# FE_Channel.net
KiCad netlist of a schematic drawn in Altium Designer
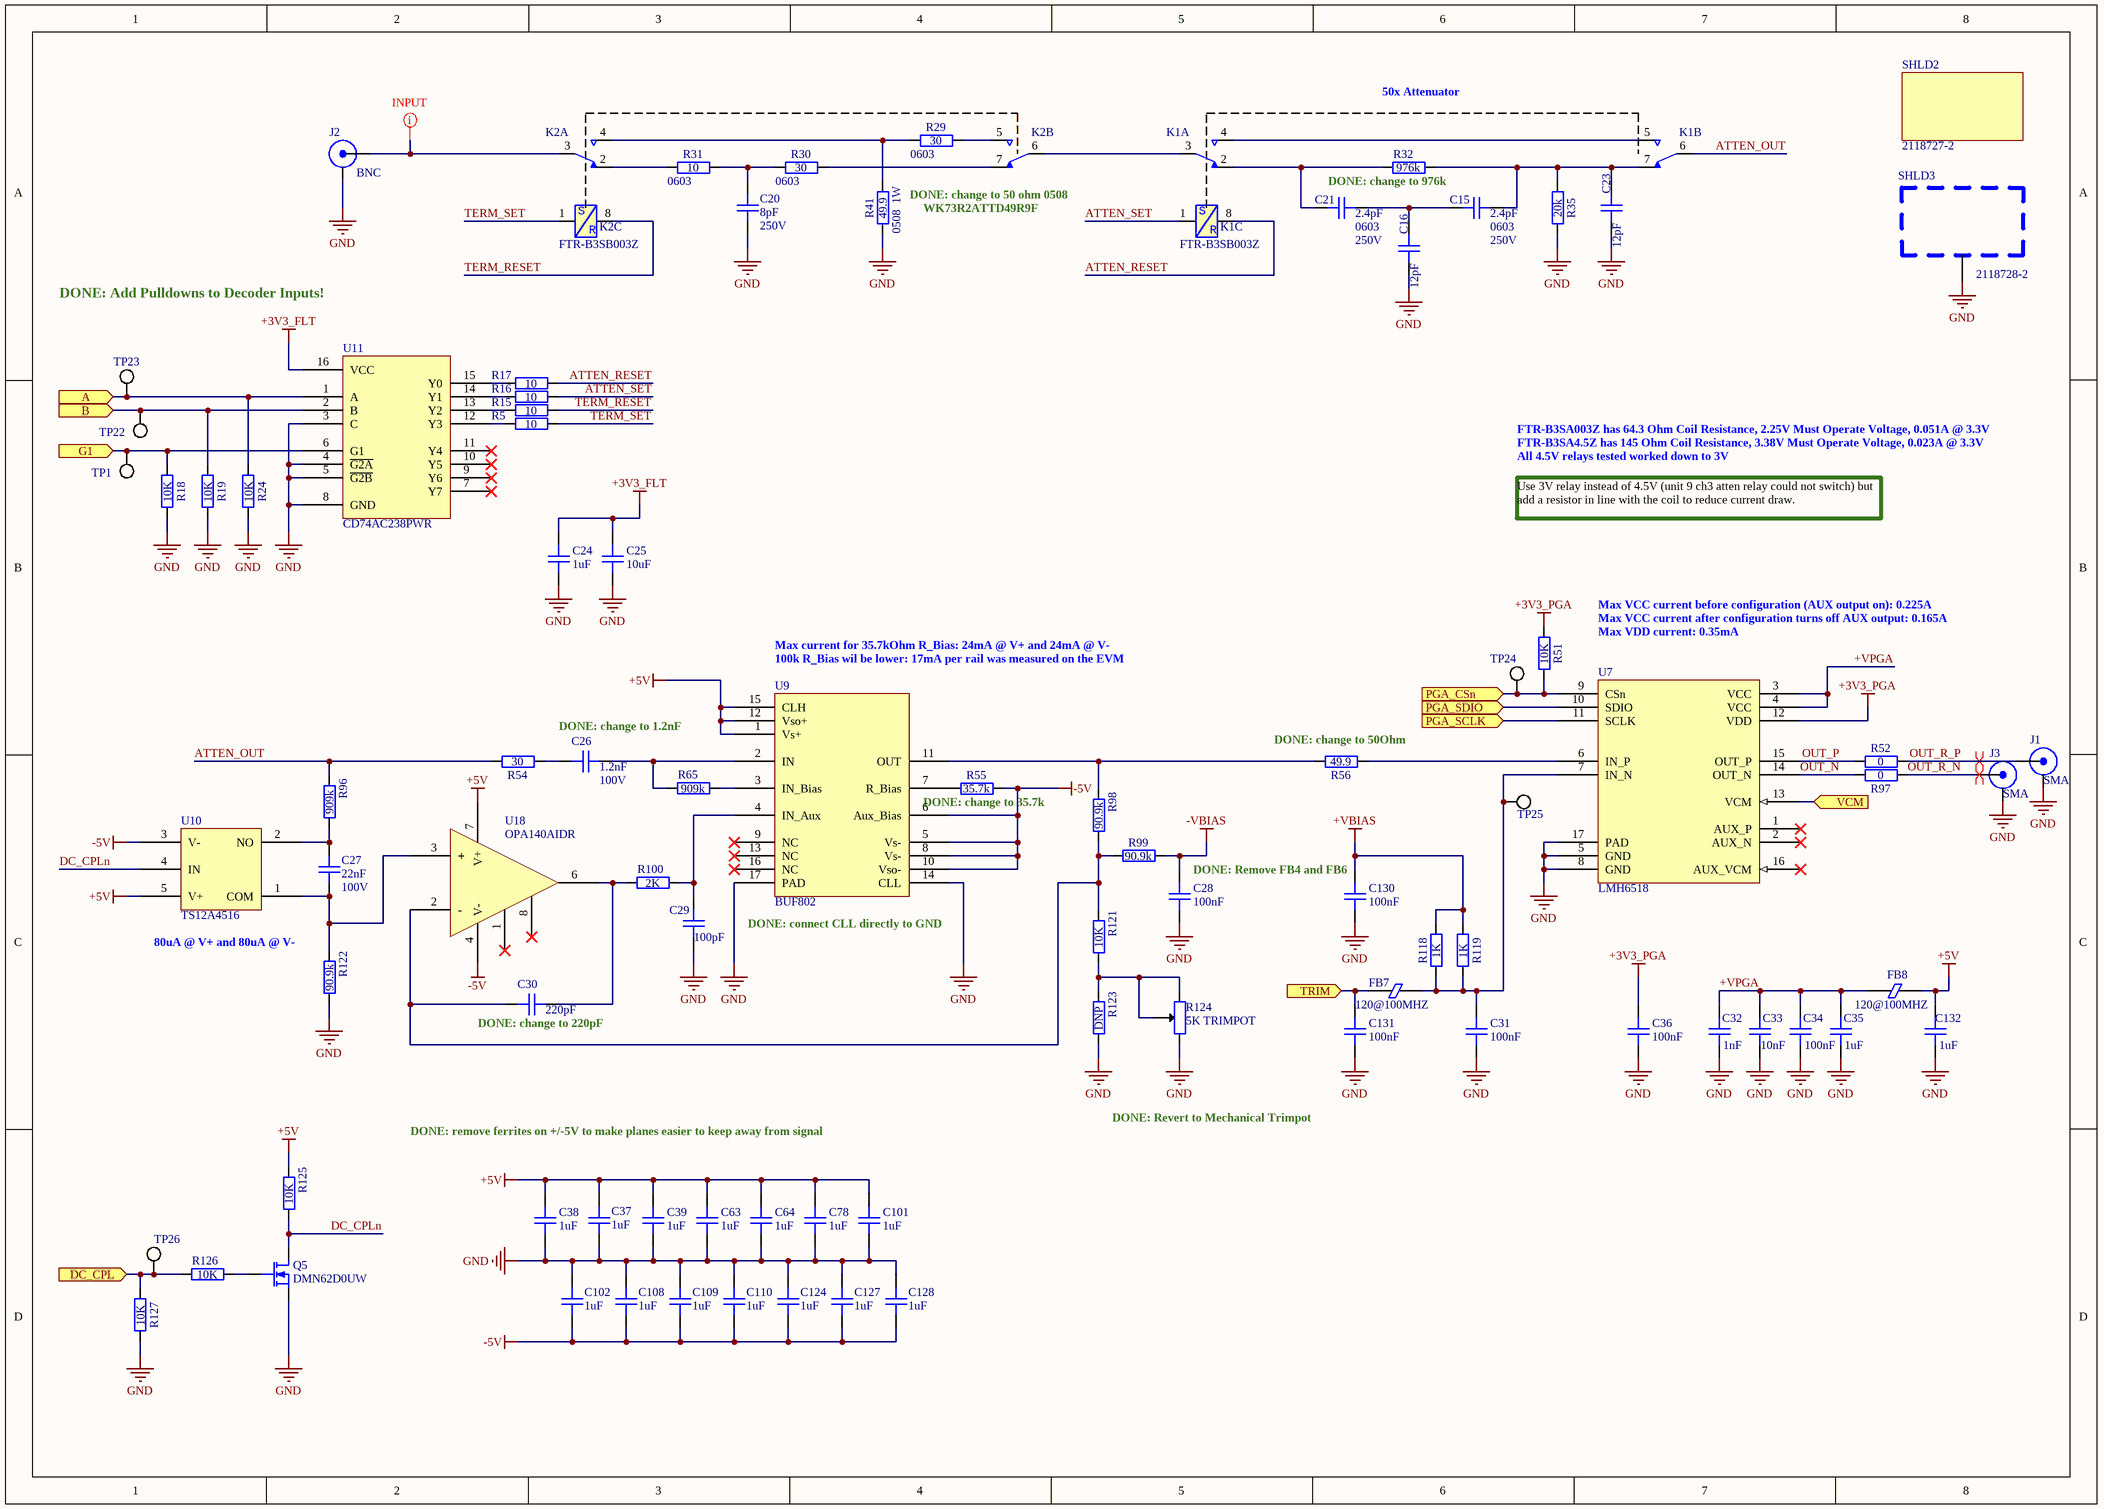
[diagram p0: FE_Channel.SchDoc]

(export (version "E")
  (design (tool "Eeschema 10.0.6"))
  (components
    (comp (ref "C15")
      (value "2.4pF")
      (footprint "GEN_C_0603")
      (fields
        (field (name "PACKAGE") "0603")
        (field (name "VOLTAGE RATING") "250V")
        (field (name "MANUFACTURER") "KEMET")
        (field (name "MANUFACTURER PART NUMBER") "CBR06C249BAGAC")
      )
      (libsource (lib "DSO") (part "CAP 2.4pF 250V C0G 0603"))
    )
    (comp (ref "C16")
      (value "12pF")
      (footprint "GEN_C_0402")
      (fields
        (field (name "MANUFACTURER") "KEMET")
        (field (name "MANUFACTURER PART NUMBER") "CBR04C120F5GAC")
      )
      (libsource (lib "DSO") (part "CAP 12pF 50V C0G 0402"))
    )
    (comp (ref "C20")
      (value "8pF")
      (footprint "GEN_C_0603")
      (fields
        (field (name "MANUFACTURER") "KEMET")
        (field (name "MANUFACTURER PART NUMBER") "CBR06C809BAGAC")
        (field (name "VOLTAGE RATING") "250V")
      )
      (libsource (lib "DSO") (part "CAP 8pF 250V C0G 0603"))
    )
    (comp (ref "C21")
      (value "2.4pF")
      (footprint "GEN_C_0603")
      (fields
        (field (name "PACKAGE") "0603")
        (field (name "VOLTAGE RATING") "250V")
        (field (name "MANUFACTURER") "KEMET")
        (field (name "MANUFACTURER PART NUMBER") "CBR06C249BAGAC")
      )
      (libsource (lib "DSO") (part "CAP 2.4pF 250V C0G 0603"))
    )
    (comp (ref "C23")
      (value "12pF")
      (footprint "GEN_C_0402")
      (fields
        (field (name "MANUFACTURER") "KEMET")
        (field (name "MANUFACTURER PART NUMBER") "CBR04C120F5GAC")
      )
      (libsource (lib "DSO") (part "CAP 12pF 50V C0G 0402"))
    )
    (comp (ref "C24")
      (value "1uF")
      (footprint "GEN_C_0402")
      (fields
        (field (name "MANUFACTURER") "Murata")
        (field (name "MANUFACTURER PART NUMBER") "GRM155R61E105KA12D")
      )
      (libsource (lib "DSO") (part "CAP 1uF 25V X5R 0402"))
    )
    (comp (ref "C25")
      (value "10uF")
      (footprint "GEN_C_0603")
      (fields
        (field (name "HOUSE PART NUMBER") "C-10uF-0603-002")
        (field (name "MANUFACTURER") "Murata")
        (field (name "MANUFACTURER PART NUMBER") "GRM188R61A106ME69D")
      )
      (libsource (lib "DSO") (part "CAP 10uF 10V X5R 0603"))
    )
    (comp (ref "C26")
      (value "1.2nF")
      (footprint "GEN_C_0603")
      (fields
        (field (name "VOLTAGE RATING") "100V")
        (field (name "MANUFACTURER") "Murata")
        (field (name "MANUFACTURER PART NUMBER") "GCM1885C2A122FA16D")
      )
      (libsource (lib "DSO") (part "CAP 1.2nF 100V C0G 0603"))
    )
    (comp (ref "C27")
      (value "22nF")
      (footprint "GEN_C_0603")
      (fields
        (field (name "VOLTAGE RATING") "100V")
        (field (name "MANUFACTURER") "Murata")
        (field (name "MANUFACTURER PART NUMBER") "GCM188R72A223KA37D")
      )
      (libsource (lib "DSO") (part "CAP 22nF 100V X7R 0603"))
    )
    (comp (ref "C28")
      (value "100nF")
      (footprint "GEN_C_0402")
      (fields
        (field (name "HOUSE PART NUMBER") "C-100nF-0402-002")
        (field (name "MANUFACTURER") "Murata")
        (field (name "MANUFACTURER PART NUMBER") "GCM155R71C104KA55D")
      )
      (libsource (lib "DSO") (part "CAP 100nF 16V X7R 0402"))
    )
    (comp (ref "C29")
      (value "100pF")
      (footprint "GEN_C_0402")
      (fields
        (field (name "MANUFACTURER") "Murata")
        (field (name "MANUFACTURER PART NUMBER") "GCM1555C1H101FA16D")
      )
      (libsource (lib "DSO") (part "CAP 100pF 50V C0G 0402"))
    )
    (comp (ref "C30")
      (value "220pF")
      (footprint "GEN_C_0402")
      (fields
        (field (name "MANUFACTURER") "Murata")
        (field (name "MANUFACTURER PART NUMBER") "GCM1555C1H221FA16J")
      )
      (libsource (lib "DSO") (part "CAP 220pF 50V C0G 0402"))
    )
    (comp (ref "C31")
      (value "100nF")
      (footprint "GEN_C_0402")
      (fields
        (field (name "HOUSE PART NUMBER") "C-100nF-0402-002")
        (field (name "MANUFACTURER") "Murata")
        (field (name "MANUFACTURER PART NUMBER") "GCM155R71C104KA55D")
      )
      (libsource (lib "DSO") (part "CAP 100nF 16V X7R 0402"))
    )
    (comp (ref "C32")
      (value "1nF")
      (footprint "GEN_C_0402")
      (fields
        (field (name "MANUFACTURER") "Murata")
        (field (name "MANUFACTURER PART NUMBER") "GRM1555C1H102FA01D")
      )
      (libsource (lib "DSO") (part "CAP 1nF 50V C0G 0402"))
    )
    (comp (ref "C33")
      (value "10nF")
      (footprint "GEN_C_0402")
      (fields
        (field (name "HOUSE PART NUMBER") "C-10nF-0402-002")
        (field (name "MANUFACTURER") "Murata")
        (field (name "MANUFACTURER PART NUMBER") "GRM155R71H103KA88J")
      )
      (libsource (lib "DSO") (part "CAP 10nF 50V X7R 0402"))
    )
    (comp (ref "C34")
      (value "100nF")
      (footprint "GEN_C_0402")
      (fields
        (field (name "HOUSE PART NUMBER") "C-100nF-0402-002")
        (field (name "MANUFACTURER") "Murata")
        (field (name "MANUFACTURER PART NUMBER") "GCM155R71C104KA55D")
      )
      (libsource (lib "DSO") (part "CAP 100nF 16V X7R 0402"))
    )
    (comp (ref "C35")
      (value "1uF")
      (footprint "GEN_C_0402")
      (fields
        (field (name "MANUFACTURER") "Murata")
        (field (name "MANUFACTURER PART NUMBER") "GRM155R61E105KA12D")
      )
      (libsource (lib "DSO") (part "CAP 1uF 25V X5R 0402"))
    )
    (comp (ref "C36")
      (value "100nF")
      (footprint "GEN_C_0402")
      (fields
        (field (name "HOUSE PART NUMBER") "C-100nF-0402-002")
        (field (name "MANUFACTURER") "Murata")
        (field (name "MANUFACTURER PART NUMBER") "GCM155R71C104KA55D")
      )
      (libsource (lib "DSO") (part "CAP 100nF 16V X7R 0402"))
    )
    (comp (ref "C37")
      (value "1uF")
      (footprint "GEN_C_0402")
      (fields
        (field (name "MANUFACTURER") "Murata")
        (field (name "MANUFACTURER PART NUMBER") "GRM155R61E105KA12D")
      )
      (libsource (lib "DSO") (part "CAP 1uF 25V X5R 0402"))
    )
    (comp (ref "C38")
      (value "1uF")
      (footprint "GEN_C_0402")
      (fields
        (field (name "MANUFACTURER") "Murata")
        (field (name "MANUFACTURER PART NUMBER") "GRM155R61E105KA12D")
      )
      (libsource (lib "DSO") (part "CAP 1uF 25V X5R 0402"))
    )
    (comp (ref "C39")
      (value "1uF")
      (footprint "GEN_C_0402")
      (fields
        (field (name "MANUFACTURER") "Murata")
        (field (name "MANUFACTURER PART NUMBER") "GRM155R61E105KA12D")
      )
      (libsource (lib "DSO") (part "CAP 1uF 25V X5R 0402"))
    )
    (comp (ref "C63")
      (value "1uF")
      (footprint "GEN_C_0402")
      (fields
        (field (name "MANUFACTURER") "Murata")
        (field (name "MANUFACTURER PART NUMBER") "GRM155R61E105KA12D")
      )
      (libsource (lib "DSO") (part "CAP 1uF 25V X5R 0402"))
    )
    (comp (ref "C64")
      (value "1uF")
      (footprint "GEN_C_0402")
      (fields
        (field (name "MANUFACTURER") "Murata")
        (field (name "MANUFACTURER PART NUMBER") "GRM155R61E105KA12D")
      )
      (libsource (lib "DSO") (part "CAP 1uF 25V X5R 0402"))
    )
    (comp (ref "C78")
      (value "1uF")
      (footprint "GEN_C_0402")
      (fields
        (field (name "MANUFACTURER") "Murata")
        (field (name "MANUFACTURER PART NUMBER") "GRM155R61E105KA12D")
      )
      (libsource (lib "DSO") (part "CAP 1uF 25V X5R 0402"))
    )
    (comp (ref "C101")
      (value "1uF")
      (footprint "GEN_C_0402")
      (fields
        (field (name "MANUFACTURER") "Murata")
        (field (name "MANUFACTURER PART NUMBER") "GRM155R61E105KA12D")
      )
      (libsource (lib "DSO") (part "CAP 1uF 25V X5R 0402"))
    )
    (comp (ref "C102")
      (value "1uF")
      (footprint "GEN_C_0402")
      (fields
        (field (name "MANUFACTURER") "Murata")
        (field (name "MANUFACTURER PART NUMBER") "GRM155R61E105KA12D")
      )
      (libsource (lib "DSO") (part "CAP 1uF 25V X5R 0402"))
    )
    (comp (ref "C108")
      (value "1uF")
      (footprint "GEN_C_0402")
      (fields
        (field (name "MANUFACTURER") "Murata")
        (field (name "MANUFACTURER PART NUMBER") "GRM155R61E105KA12D")
      )
      (libsource (lib "DSO") (part "CAP 1uF 25V X5R 0402"))
    )
    (comp (ref "C109")
      (value "1uF")
      (footprint "GEN_C_0402")
      (fields
        (field (name "MANUFACTURER") "Murata")
        (field (name "MANUFACTURER PART NUMBER") "GRM155R61E105KA12D")
      )
      (libsource (lib "DSO") (part "CAP 1uF 25V X5R 0402"))
    )
    (comp (ref "C110")
      (value "1uF")
      (footprint "GEN_C_0402")
      (fields
        (field (name "MANUFACTURER") "Murata")
        (field (name "MANUFACTURER PART NUMBER") "GRM155R61E105KA12D")
      )
      (libsource (lib "DSO") (part "CAP 1uF 25V X5R 0402"))
    )
    (comp (ref "C124")
      (value "1uF")
      (footprint "GEN_C_0402")
      (fields
        (field (name "MANUFACTURER") "Murata")
        (field (name "MANUFACTURER PART NUMBER") "GRM155R61E105KA12D")
      )
      (libsource (lib "DSO") (part "CAP 1uF 25V X5R 0402"))
    )
    (comp (ref "C127")
      (value "1uF")
      (footprint "GEN_C_0402")
      (fields
        (field (name "MANUFACTURER") "Murata")
        (field (name "MANUFACTURER PART NUMBER") "GRM155R61E105KA12D")
      )
      (libsource (lib "DSO") (part "CAP 1uF 25V X5R 0402"))
    )
    (comp (ref "C128")
      (value "1uF")
      (footprint "GEN_C_0402")
      (fields
        (field (name "MANUFACTURER") "Murata")
        (field (name "MANUFACTURER PART NUMBER") "GRM155R61E105KA12D")
      )
      (libsource (lib "DSO") (part "CAP 1uF 25V X5R 0402"))
    )
    (comp (ref "C130")
      (value "100nF")
      (footprint "GEN_C_0402")
      (fields
        (field (name "HOUSE PART NUMBER") "C-100nF-0402-002")
        (field (name "MANUFACTURER") "Murata")
        (field (name "MANUFACTURER PART NUMBER") "GCM155R71C104KA55D")
      )
      (libsource (lib "DSO") (part "CAP 100nF 16V X7R 0402"))
    )
    (comp (ref "C131")
      (value "100nF")
      (footprint "GEN_C_0402")
      (fields
        (field (name "HOUSE PART NUMBER") "C-100nF-0402-002")
        (field (name "MANUFACTURER") "Murata")
        (field (name "MANUFACTURER PART NUMBER") "GCM155R71C104KA55D")
      )
      (libsource (lib "DSO") (part "CAP 100nF 16V X7R 0402"))
    )
    (comp (ref "C132")
      (value "1uF")
      (footprint "GEN_C_0402")
      (fields
        (field (name "MANUFACTURER") "Murata")
        (field (name "MANUFACTURER PART NUMBER") "GRM155R61E105KA12D")
      )
      (libsource (lib "DSO") (part "CAP 1uF 25V X5R 0402"))
    )
    (comp (ref "FB7")
      (value "120@100MHZ")
      (footprint "GEN_R_0402")
      (fields (field (name "HOUSE PART NUMBER") "BLM15PX121SN1D") (field (name "MANUFACTURER") "Murata"))
      (libsource (lib "DSO") (part "FERRITE BEAD 120 OHM 0402"))
    )
    (comp (ref "FB8")
      (value "120@100MHZ")
      (footprint "GEN_R_0402")
      (fields (field (name "HOUSE PART NUMBER") "BLM15PX121SN1D") (field (name "MANUFACTURER") "Murata"))
      (libsource (lib "DSO") (part "FERRITE BEAD 120 OHM 0402"))
    )
    (comp (ref "J1")
      (value "SMA")
      (footprint "MOL_0733910083")
      (fields (field (name "MANUFACTURER") "Molex") (field (name "MANUFACTURER PART NUMBER") "73100-0105"))
      (libsource (lib "DSO") (part "SMA JACK R/A"))
    )
    (comp (ref "J2")
      (value "BNC")
      (footprint "MOL_0731000105")
      (fields (field (name "MANUFACTURER") "Molex") (field (name "MANUFACTURER PART NUMBER") "73100-0105"))
      (libsource (lib "DSO") (part "BNC JACK R/A"))
    )
    (comp (ref "J3")
      (value "SMA")
      (footprint "MOL_0733910083")
      (fields (field (name "MANUFACTURER") "Molex") (field (name "MANUFACTURER PART NUMBER") "73100-0105"))
      (libsource (lib "DSO") (part "SMA JACK R/A"))
    )
    (comp (ref "K1")
      (value "FTR-B3SB003Z")
      (footprint "FUJ_FTR-B3SA")
      (fields (field (name "MANUFACTURER") "Fujitsu"))
      (libsource (lib "") (part "RELAY DPDT-NO FTR-B3SB003Z_1"))
    )
    (comp (ref "K2")
      (value "FTR-B3SB003Z")
      (footprint "FUJ_FTR-B3SA")
      (fields (field (name "MANUFACTURER") "Fujitsu"))
      (libsource (lib "") (part "RELAY DPDT-NO FTR-B3SB003Z_1"))
    )
    (comp (ref "Q5")
      (value "DMN62D0UW")
      (footprint "GEN_SOT_323")
      (fields (field (name "HOUSE PART NUMBER") "DMN62D0UW-7") (field (name "MANUFACTURER") "Diodes"))
      (libsource (lib "DSO") (part "NMOS DMN62D0UW"))
    )
    (comp (ref "R5")
      (value "10")
      (footprint "GEN_R_0603")
      (fields
        (field (name "TOLERANCE") "1%")
        (field (name "MANUFACTURER") "KOA Speer")
        (field (name "MANUFACTURER PART NUMBER") "SG73P1JTTD10R0F")
      )
      (libsource (lib "DSO") (part "RES 10 OHM 1% 1/3W 0603"))
    )
    (comp (ref "R15")
      (value "10")
      (footprint "GEN_R_0603")
      (fields
        (field (name "TOLERANCE") "1%")
        (field (name "MANUFACTURER") "KOA Speer")
        (field (name "MANUFACTURER PART NUMBER") "SG73P1JTTD10R0F")
      )
      (libsource (lib "DSO") (part "RES 10 OHM 1% 1/3W 0603"))
    )
    (comp (ref "R16")
      (value "10")
      (footprint "GEN_R_0603")
      (fields
        (field (name "TOLERANCE") "1%")
        (field (name "MANUFACTURER") "KOA Speer")
        (field (name "MANUFACTURER PART NUMBER") "SG73P1JTTD10R0F")
      )
      (libsource (lib "DSO") (part "RES 10 OHM 1% 1/3W 0603"))
    )
    (comp (ref "R17")
      (value "10")
      (footprint "GEN_R_0603")
      (fields
        (field (name "TOLERANCE") "1%")
        (field (name "MANUFACTURER") "KOA Speer")
        (field (name "MANUFACTURER PART NUMBER") "SG73P1JTTD10R0F")
      )
      (libsource (lib "DSO") (part "RES 10 OHM 1% 1/3W 0603"))
    )
    (comp (ref "R18")
      (value "10K")
      (footprint "GEN_R_0402")
      (fields
        (field (name "TOLERANCE") "1%")
        (field (name "MANUFACTURER") "Panasonic")
        (field (name "MANUFACTURER PART NUMBER") "ERJ-2RKF1002X")
      )
      (libsource (lib "") (part "RES 10K OHM 1% 1/10W 0402_1"))
    )
    (comp (ref "R19")
      (value "10K")
      (footprint "GEN_R_0402")
      (fields
        (field (name "TOLERANCE") "1%")
        (field (name "MANUFACTURER") "Panasonic")
        (field (name "MANUFACTURER PART NUMBER") "ERJ-2RKF1002X")
      )
      (libsource (lib "") (part "RES 10K OHM 1% 1/10W 0402_1"))
    )
    (comp (ref "R24")
      (value "10K")
      (footprint "GEN_R_0402")
      (fields
        (field (name "TOLERANCE") "1%")
        (field (name "MANUFACTURER") "Panasonic")
        (field (name "MANUFACTURER PART NUMBER") "ERJ-2RKF1002X")
      )
      (libsource (lib "") (part "RES 10K OHM 1% 1/10W 0402_1"))
    )
    (comp (ref "R29")
      (value "30")
      (footprint "GEN_R_0603")
      (fields
        (field (name "TOLERANCE") "1%")
        (field (name "PACKAGE") "0603")
        (field (name "MANUFACTURER") "KOA Speer")
        (field (name "MANUFACTURER PART NUMBER") "SG73P1JTTD30R0F")
      )
      (libsource (lib "DSO") (part "RES 30 OHM 1% 1/3W 0603"))
    )
    (comp (ref "R30")
      (value "30")
      (footprint "GEN_R_0603")
      (fields
        (field (name "TOLERANCE") "1%")
        (field (name "PACKAGE") "0603")
        (field (name "MANUFACTURER") "KOA Speer")
        (field (name "MANUFACTURER PART NUMBER") "SG73P1JTTD30R0F")
      )
      (libsource (lib "DSO") (part "RES 30 OHM 1% 1/3W 0603"))
    )
    (comp (ref "R31")
      (value "10")
      (footprint "GEN_R_0603")
      (fields
        (field (name "TOLERANCE") "1%")
        (field (name "PACKAGE") "0603")
        (field (name "MANUFACTURER") "KOA Speer")
        (field (name "MANUFACTURER PART NUMBER") "SG73P1JTTD10R0F")
      )
      (libsource (lib "") (part "RES 10 OHM 1% 1/3W 0603_1"))
    )
    (comp (ref "R32")
      (value "976k")
      (footprint "GEN_R_0603")
      (fields
        (field (name "MANUFACTURER") "KOA Speer")
        (field (name "MANUFACTURER PART NUMBER") "RK73H1JTTD9763F")
        (field (name "TOLERANCE") "1%")
      )
      (libsource (lib "DSO") (part "RES 976k OHM 1% 1/10W 0603"))
    )
    (comp (ref "R35")
      (value "20k")
      (footprint "GEN_R_0402")
      (fields
        (field (name "TOLERANCE") "1%")
        (field (name "MANUFACTURER") "Yageo")
        (field (name "MANUFACTURER PART NUMBER") "RC0402FR-0720KL")
      )
      (libsource (lib "DSO") (part "RES 20K OHM 1% 1/16W 0402"))
    )
    (comp (ref "R41")
      (value "49.9")
      (footprint "GEN_R_0508")
      (fields
        (field (name "TOLERANCE") "1%")
        (field (name "PACKAGE") "0508")
        (field (name "MANUFACTURER") "KOA Speer")
        (field (name "MANUFACTURER PART NUMBER") "WK73R2ATTD49R9F")
        (field (name "POWER RATING") "1W")
      )
      (libsource (lib "DSO") (part "RES 49.9 OHM 1% 1W 0508"))
    )
    (comp (ref "R51")
      (value "10K")
      (footprint "GEN_R_0402")
      (fields
        (field (name "TOLERANCE") "1%")
        (field (name "MANUFACTURER") "Panasonic")
        (field (name "MANUFACTURER PART NUMBER") "ERJ-2RKF1002X")
      )
      (libsource (lib "DSO") (part "RES 10K OHM 1% 1/10W 0402"))
    )
    (comp (ref "R52")
      (value "0")
      (footprint "GEN_R_0402")
      (fields
        (field (name "MANUFACTURER") "Yageo")
        (field (name "MANUFACTURER PART NUMBER") "RC0402JR-070RL")
      )
      (libsource (lib "DSO") (part "RES 0 OHM 1/16W 0402"))
    )
    (comp (ref "R54")
      (value "30")
      (footprint "GEN_R_0603")
      (fields
        (field (name "TOLERANCE") "1%")
        (field (name "MANUFACTURER") "KOA Speer")
        (field (name "MANUFACTURER PART NUMBER") "SG73P1JTTD30R0F")
      )
      (libsource (lib "DSO") (part "RES 30 OHM 1% 1/3W 0603"))
    )
    (comp (ref "R55")
      (value "35.7k")
      (footprint "GEN_R_0402")
      (fields
        (field (name "TOLERANCE") "1%")
        (field (name "MANUFACTURER") "Yageo")
        (field (name "MANUFACTURER PART NUMBER") "RC0402FR-0735K7L")
      )
      (libsource (lib "DSO") (part "RES 35.7K OHM 1% 1/16W 0402"))
    )
    (comp (ref "R56")
      (value "49.9")
      (footprint "GEN_R_0402")
      (fields
        (field (name "MANUFACTURER") "Yageo")
        (field (name "MANUFACTURER PART NUMBER") "RC0402FR-0749R9L")
        (field (name "TOLERANCE") "1%")
      )
      (libsource (lib "DSO") (part "RES 49.9 OHM 1% 1/10W 0402"))
    )
    (comp (ref "R65")
      (value "909k")
      (footprint "GEN_R_0402")
      (fields
        (field (name "TOLERANCE") "1%")
        (field (name "MANUFACTURER") "Yageo")
        (field (name "MANUFACTURER PART NUMBER") "RC0402FR-07909KL")
      )
      (libsource (lib "") (part "RES 909K OHM 1% 1/16W 0402_1"))
    )
    (comp (ref "R96")
      (value "909k")
      (footprint "GEN_R_0402")
      (fields
        (field (name "TOLERANCE") "1%")
        (field (name "MANUFACTURER") "Yageo")
        (field (name "MANUFACTURER PART NUMBER") "RC0402FR-07909KL")
      )
      (libsource (lib "DSO") (part "RES 909K OHM 1% 1/16W 0402"))
    )
    (comp (ref "R97")
      (value "0")
      (footprint "GEN_R_0402")
      (fields
        (field (name "MANUFACTURER") "Yageo")
        (field (name "MANUFACTURER PART NUMBER") "RC0402JR-070RL")
      )
      (libsource (lib "DSO") (part "RES 0 OHM 1/16W 0402"))
    )
    (comp (ref "R98")
      (value "90.9k")
      (footprint "GEN_R_0402")
      (fields
        (field (name "TOLERANCE") "1%")
        (field (name "MANUFACTURER") "Yageo")
        (field (name "MANUFACTURER PART NUMBER") "RC0402FR-0790K9L")
      )
      (libsource (lib "DSO") (part "RES 90.9K OHM 1% 1/16W 0402"))
    )
    (comp (ref "R99")
      (value "90.9k")
      (footprint "GEN_R_0402")
      (fields
        (field (name "TOLERANCE") "1%")
        (field (name "MANUFACTURER") "Yageo")
        (field (name "MANUFACTURER PART NUMBER") "RC0402FR-0790K9L")
      )
      (libsource (lib "") (part "RES 90.9K OHM 1% 1/16W 0402_1"))
    )
    (comp (ref "R100")
      (value "2K")
      (footprint "GEN_R_0402")
      (fields
        (field (name "TOLERANCE") "1%")
        (field (name "MANUFACTURER") "Yageo")
        (field (name "MANUFACTURER PART NUMBER") "RC0402FR-072KL")
      )
      (libsource (lib "DSO") (part "RES 2K OHM 1% 1/16W 0402"))
    )
    (comp (ref "R118")
      (value "1K")
      (footprint "GEN_R_0402")
      (fields
        (field (name "TOLERANCE") "1%")
        (field (name "HOUSE PART NUMBER") "R-1K-0402-1%-001")
        (field (name "MANUFACTURER") "Yageo")
      )
      (libsource (lib "DSO") (part "RES 1K OHM 1% 1/10W 0402"))
    )
    (comp (ref "R119")
      (value "1K")
      (footprint "GEN_R_0402")
      (fields
        (field (name "TOLERANCE") "1%")
        (field (name "HOUSE PART NUMBER") "R-1K-0402-1%-001")
        (field (name "MANUFACTURER") "Yageo")
      )
      (libsource (lib "") (part "RES 1K OHM 1% 1/10W 0402_1"))
    )
    (comp (ref "R121")
      (value "10K")
      (footprint "GEN_R_0402")
      (fields
        (field (name "TOLERANCE") "1%")
        (field (name "MANUFACTURER") "Panasonic")
        (field (name "MANUFACTURER PART NUMBER") "ERJ-2RKF1002X")
      )
      (libsource (lib "DSO") (part "RES 10K OHM 1% 1/10W 0402"))
    )
    (comp (ref "R122")
      (value "90.9k")
      (footprint "GEN_R_0402")
      (fields
        (field (name "TOLERANCE") "1%")
        (field (name "MANUFACTURER") "Yageo")
        (field (name "MANUFACTURER PART NUMBER") "RC0402FR-0790K9L")
      )
      (libsource (lib "DSO") (part "RES 90.9K OHM 1% 1/16W 0402"))
    )
    (comp (ref "R123")
      (value "DNP")
      (footprint "GEN_R_0402")
      (fields (field (name "TOLERANCE") "1%"))
      (libsource (lib "DSO") (part "RES DNP 0402"))
    )
    (comp (ref "R124")
      (value "5K TRIMPOT")
      (footprint "BOU_3mm_POT")
      (fields
        (field (name "TOLERANCE") "1%")
        (field (name "MANUFACTURER") "Bourns")
        (field (name "MANUFACTURER PART NUMBER") "TC33X-2-502E")
      )
      (libsource (lib "DSO") (part "TRIMMER 5K OHM 0.1W J LEAD TOP"))
    )
    (comp (ref "R125")
      (value "10K")
      (footprint "GEN_R_0402")
      (fields
        (field (name "TOLERANCE") "1%")
        (field (name "MANUFACTURER") "Panasonic")
        (field (name "MANUFACTURER PART NUMBER") "ERJ-2RKF1002X")
      )
      (libsource (lib "DSO") (part "RES 10K OHM 1% 1/10W 0402"))
    )
    (comp (ref "R126")
      (value "10K")
      (footprint "GEN_R_0402")
      (fields
        (field (name "TOLERANCE") "1%")
        (field (name "MANUFACTURER") "Panasonic")
        (field (name "MANUFACTURER PART NUMBER") "ERJ-2RKF1002X")
      )
      (libsource (lib "") (part "RES 10K OHM 1% 1/10W 0402_2"))
    )
    (comp (ref "R127")
      (value "10K")
      (footprint "GEN_R_0402")
      (fields
        (field (name "TOLERANCE") "1%")
        (field (name "MANUFACTURER") "Panasonic")
        (field (name "MANUFACTURER PART NUMBER") "ERJ-2RKF1002X")
      )
      (libsource (lib "") (part "RES 10K OHM 1% 1/10W 0402_1"))
    )
    (comp (ref "SHLD2")
      (value "2118727-2")
      (fields (field (name "MANUFACTURER") "TE Connectivity AMP"))
      (libsource (lib "DSO") (part "SHIELD 2118727-2"))
    )
    (comp (ref "SHLD3")
      (value "2118728-2")
      (footprint "TE_2118728-2")
      (fields (field (name "MANUFACTURER") "TE Connectivity"))
      (libsource (lib "DSO") (part "SHIELD 2118728-2"))
    )
    (comp (ref "TP1") (value "PCB") (footprint "GEN_TP_PCB") (libsource (lib "DSO") (part "TP PCB 1mm")))
    (comp (ref "TP22") (value "PCB") (footprint "GEN_TP_PCB") (libsource (lib "DSO") (part "TP PCB 1mm")))
    (comp (ref "TP23") (value "PCB") (footprint "GEN_TP_PCB") (libsource (lib "DSO") (part "TP PCB 1mm")))
    (comp (ref "TP24") (value "PCB") (footprint "GEN_TP_PCB") (libsource (lib "DSO") (part "TP PCB 1mm")))
    (comp (ref "TP25") (value "PCB") (footprint "GEN_TP_PCB") (libsource (lib "DSO") (part "TP PCB 1mm")))
    (comp (ref "TP26") (value "PCB") (footprint "GEN_TP_PCB") (libsource (lib "DSO") (part "TP PCB 1mm")))
    (comp (ref "U7")
      (value "LMH6518")
      (footprint "TI_WQFN_RGH0016A")
      (fields
        (field (name "MANUFACTURER") "Texas Instruments")
        (field (name "MANUFACTURER PART NUMBER") "LMH6518SQE/NOPB")
      )
      (libsource (lib "DSO") (part "IC PGA LMH6518"))
    )
    (comp (ref "U9")
      (value "BUF802")
      (footprint "TI_VQFN_RGT0016C")
      (fields
        (field (name "MANUFACTURER") "Texas Instruments")
        (field (name "MANUFACTURER PART NUMBER") "BUF802IRGTR")
      )
      (libsource (lib "DSO") (part "IC BUFFER AMP BUF802"))
    )
    (comp (ref "U10")
      (value "TS12A4516")
      (footprint "GEN_SOT23_5_950_2900X1600X1450")
      (fields
        (field (name "MANUFACTURER") "Texas Instruments")
        (field (name "MANUFACTURER PART NUMBER") "TS12A4516DBVR")
      )
      (libsource (lib "DSO") (part "IC SWITCH SPST TS12A4516DBVR"))
    )
    (comp (ref "U11")
      (value "CD74AC238PWR")
      (footprint "TI_TSSOP16_PW0016A")
      (fields (field (name "MANUFACTURER") "Texas Instruments"))
      (libsource (lib "DSO") (part "IC Decoder CD74AC238"))
    )
    (comp (ref "U18")
      (value "OPA140AIDR")
      (footprint "TI_SOIC8_D0008A")
      (fields (field (name "MANUFACTURER") "Texas Instruments"))
      (libsource (lib "DSO") (part "IC OPAMP OPA140"))
    )
  )
  (nets
    (net (code "1") (name "+3V3_FLT") (class "Default")
      (node (ref "C24") (pin "2") (pinfunction "2_2") (pintype "passive"))
      (node (ref "C25") (pin "2") (pinfunction "2_2") (pintype "passive"))
      (node (ref "U11") (pin "16") (pinfunction "VCC_16") (pintype "passive"))
    )
    (net (code "2") (name "+3V3_PGA") (class "Default")
      (node (ref "C36") (pin "2") (pinfunction "2_2") (pintype "passive"))
      (node (ref "R51") (pin "2") (pinfunction "2_2") (pintype "passive"))
      (node (ref "U7") (pin "12") (pinfunction "VDD_12") (pintype "power_in"))
    )
    (net (code "3") (name "+5V") (class "Default")
      (node (ref "C101") (pin "2") (pinfunction "2_2") (pintype "passive"))
      (node (ref "C132") (pin "2") (pinfunction "2_2") (pintype "passive"))
      (node (ref "C37") (pin "2") (pinfunction "2_2") (pintype "passive"))
      (node (ref "C38") (pin "1") (pinfunction "1_1") (pintype "passive"))
      (node (ref "C39") (pin "1") (pinfunction "1_1") (pintype "passive"))
      (node (ref "C63") (pin "1") (pinfunction "1_1") (pintype "passive"))
      (node (ref "C64") (pin "2") (pinfunction "2_2") (pintype "passive"))
      (node (ref "C78") (pin "2") (pinfunction "2_2") (pintype "passive"))
      (node (ref "FB8") (pin "2") (pinfunction "2_2") (pintype "passive"))
      (node (ref "R125") (pin "2") (pinfunction "2_2") (pintype "passive"))
      (node (ref "U10") (pin "5") (pinfunction "V+_5") (pintype "passive"))
      (node (ref "U18") (pin "7") (pinfunction "V+_7") (pintype "passive"))
      (node (ref "U9") (pin "1") (pinfunction "Vs+_1") (pintype "passive"))
      (node (ref "U9") (pin "12") (pinfunction "Vso+_12") (pintype "passive"))
      (node (ref "U9") (pin "15") (pinfunction "CLH_15") (pintype "passive"))
    )
    (net (code "4") (name "+VBIAS") (class "Default")
      (node (ref "C130") (pin "1") (pinfunction "1_1") (pintype "passive"))
      (node (ref "R118") (pin "2") (pinfunction "2_2") (pintype "passive"))
      (node (ref "R119") (pin "1") (pinfunction "1_1") (pintype "passive"))
    )
    (net (code "5") (name "-5V") (class "Default")
      (node (ref "C102") (pin "2") (pinfunction "2_2") (pintype "passive"))
      (node (ref "C108") (pin "2") (pinfunction "2_2") (pintype "passive"))
      (node (ref "C109") (pin "1") (pinfunction "1_1") (pintype "passive"))
      (node (ref "C110") (pin "1") (pinfunction "1_1") (pintype "passive"))
      (node (ref "C124") (pin "1") (pinfunction "1_1") (pintype "passive"))
      (node (ref "C127") (pin "2") (pinfunction "2_2") (pintype "passive"))
      (node (ref "C128") (pin "2") (pinfunction "2_2") (pintype "passive"))
      (node (ref "R55") (pin "2") (pinfunction "2_2") (pintype "passive"))
      (node (ref "U10") (pin "3") (pinfunction "V-_3") (pintype "passive"))
      (node (ref "U18") (pin "4") (pinfunction "V-_4") (pintype "passive"))
      (node (ref "U9") (pin "10") (pinfunction "Vso-_10") (pintype "passive"))
      (node (ref "U9") (pin "5") (pinfunction "Vs-_5") (pintype "passive"))
      (node (ref "U9") (pin "6") (pinfunction "Aux_Bias_6") (pintype "passive"))
      (node (ref "U9") (pin "8") (pinfunction "Vs-_8") (pintype "passive"))
    )
    (net (code "6") (name "-VBIAS") (class "Default")
      (node (ref "C28") (pin "1") (pinfunction "1_1") (pintype "passive"))
      (node (ref "R99") (pin "1") (pinfunction "1_1") (pintype "passive"))
    )
    (net (code "7") (name "/+VPGA") (class "Default")
      (node (ref "C32") (pin "2") (pinfunction "2_2") (pintype "passive"))
      (node (ref "C33") (pin "2") (pinfunction "2_2") (pintype "passive"))
      (node (ref "C34") (pin "2") (pinfunction "2_2") (pintype "passive"))
      (node (ref "C35") (pin "2") (pinfunction "2_2") (pintype "passive"))
      (node (ref "FB8") (pin "1") (pinfunction "1_1") (pintype "passive"))
      (node (ref "U7") (pin "3") (pinfunction "VCC_3") (pintype "power_in"))
      (node (ref "U7") (pin "4") (pinfunction "VCC_4") (pintype "power_in"))
    )
    (net (code "8") (name "/A") (class "Default")
      (node (ref "R24") (pin "2") (pinfunction "2_2") (pintype "passive"))
      (node (ref "TP23") (pin "1") (pinfunction "1_1") (pintype "passive"))
      (node (ref "U11") (pin "1") (pinfunction "A_1") (pintype "passive"))
    )
    (net (code "9") (name "/ATTEN_OUT") (class "Default")
      (node (ref "K1") (pin "6") (pinfunction "6_6") (pintype "passive"))
      (node (ref "R54") (pin "1") (pinfunction "1_1") (pintype "passive"))
      (node (ref "R96") (pin "2") (pinfunction "2_2") (pintype "passive"))
    )
    (net (code "10") (name "/ATTEN_RESET") (class "Default")
      (node (ref "K1") (pin "8") (pinfunction "8_8") (pintype "passive"))
      (node (ref "R17") (pin "2") (pinfunction "2_2") (pintype "passive"))
    )
    (net (code "11") (name "/ATTEN_SET") (class "Default")
      (node (ref "K1") (pin "1") (pinfunction "1_1") (pintype "passive"))
      (node (ref "R16") (pin "2") (pinfunction "2_2") (pintype "passive"))
    )
    (net (code "12") (name "/B") (class "Default")
      (node (ref "R19") (pin "2") (pinfunction "2_2") (pintype "passive"))
      (node (ref "TP22") (pin "1") (pinfunction "1_1") (pintype "passive"))
      (node (ref "U11") (pin "2") (pinfunction "B_2") (pintype "passive"))
    )
    (net (code "13") (name "/DC_CPL") (class "Default")
      (node (ref "R126") (pin "2") (pinfunction "2_2") (pintype "passive"))
      (node (ref "R127") (pin "2") (pinfunction "2_2") (pintype "passive"))
      (node (ref "TP26") (pin "1") (pinfunction "1_1") (pintype "passive"))
    )
    (net (code "14") (name "/DC_CPLn") (class "Default")
      (node (ref "Q5") (pin "1") (pinfunction "D_1") (pintype "passive"))
      (node (ref "R125") (pin "1") (pinfunction "1_1") (pintype "passive"))
      (node (ref "U10") (pin "4") (pinfunction "IN_4") (pintype "passive"))
    )
    (net (code "15") (name "/G1") (class "Default")
      (node (ref "R18") (pin "2") (pinfunction "2_2") (pintype "passive"))
      (node (ref "TP1") (pin "1") (pinfunction "1_1") (pintype "passive"))
      (node (ref "U11") (pin "6") (pinfunction "G1_6") (pintype "passive"))
    )
    (net (code "16") (name "/OUT_N") (class "Default")
      (node (ref "R97") (pin "1") (pinfunction "1_1") (pintype "passive"))
      (node (ref "U7") (pin "14") (pinfunction "OUT_N_14") (pintype "passive"))
    )
    (net (code "17") (name "/OUT_P") (class "Default")
      (node (ref "R52") (pin "1") (pinfunction "1_1") (pintype "passive"))
      (node (ref "U7") (pin "15") (pinfunction "OUT_P_15") (pintype "passive"))
    )
    (net (code "18") (name "/OUT_R_N") (class "Default")
      (node (ref "J3") (pin "1") (pinfunction "Signal_1") (pintype "passive"))
      (node (ref "R97") (pin "2") (pinfunction "2_2") (pintype "passive"))
    )
    (net (code "19") (name "/OUT_R_P") (class "Default")
      (node (ref "J1") (pin "1") (pinfunction "Signal_1") (pintype "passive"))
      (node (ref "R52") (pin "2") (pinfunction "2_2") (pintype "passive"))
    )
    (net (code "20") (name "/PGA_CSn") (class "Default")
      (node (ref "R51") (pin "1") (pinfunction "1_1") (pintype "passive"))
      (node (ref "TP24") (pin "1") (pinfunction "1_1") (pintype "passive"))
      (node (ref "U7") (pin "9") (pinfunction "CSn_9") (pintype "passive"))
    )
    (net (code "21") (name "/PGA_SCLK") (class "Default")
      (node (ref "U7") (pin "11") (pinfunction "SCLK_11") (pintype "passive"))
    )
    (net (code "22") (name "/PGA_SDIO") (class "Default")
      (node (ref "U7") (pin "10") (pinfunction "SDIO_10") (pintype "passive"))
    )
    (net (code "23") (name "/TERM_RESET") (class "Default")
      (node (ref "K2") (pin "8") (pinfunction "8_8") (pintype "passive"))
      (node (ref "R15") (pin "2") (pinfunction "2_2") (pintype "passive"))
    )
    (net (code "24") (name "/TERM_SET") (class "Default")
      (node (ref "K2") (pin "1") (pinfunction "1_1") (pintype "passive"))
      (node (ref "R5") (pin "2") (pinfunction "2_2") (pintype "passive"))
    )
    (net (code "25") (name "/TRIM") (class "Default")
      (node (ref "C131") (pin "1") (pinfunction "1_1") (pintype "passive"))
      (node (ref "FB7") (pin "1") (pinfunction "1_1") (pintype "passive"))
    )
    (net (code "26") (name "/VCM") (class "Default")
      (node (ref "U7") (pin "13") (pinfunction "VCM_13") (pintype "input"))
    )
    (net (code "27") (name "GND") (class "Default")
      (node (ref "C101") (pin "1") (pinfunction "1_1") (pintype "passive"))
      (node (ref "C102") (pin "1") (pinfunction "1_1") (pintype "passive"))
      (node (ref "C108") (pin "1") (pinfunction "1_1") (pintype "passive"))
      (node (ref "C109") (pin "2") (pinfunction "2_2") (pintype "passive"))
      (node (ref "C110") (pin "2") (pinfunction "2_2") (pintype "passive"))
      (node (ref "C124") (pin "2") (pinfunction "2_2") (pintype "passive"))
      (node (ref "C127") (pin "1") (pinfunction "1_1") (pintype "passive"))
      (node (ref "C128") (pin "1") (pinfunction "1_1") (pintype "passive"))
      (node (ref "C130") (pin "2") (pinfunction "2_2") (pintype "passive"))
      (node (ref "C131") (pin "2") (pinfunction "2_2") (pintype "passive"))
      (node (ref "C132") (pin "1") (pinfunction "1_1") (pintype "passive"))
      (node (ref "C16") (pin "1") (pinfunction "1_1") (pintype "passive"))
      (node (ref "C20") (pin "2") (pinfunction "2_2") (pintype "passive"))
      (node (ref "C23") (pin "1") (pinfunction "1_1") (pintype "passive"))
      (node (ref "C24") (pin "1") (pinfunction "1_1") (pintype "passive"))
      (node (ref "C25") (pin "1") (pinfunction "1_1") (pintype "passive"))
      (node (ref "C28") (pin "2") (pinfunction "2_2") (pintype "passive"))
      (node (ref "C29") (pin "1") (pinfunction "1_1") (pintype "passive"))
      (node (ref "C31") (pin "2") (pinfunction "2_2") (pintype "passive"))
      (node (ref "C32") (pin "1") (pinfunction "1_1") (pintype "passive"))
      (node (ref "C33") (pin "1") (pinfunction "1_1") (pintype "passive"))
      (node (ref "C34") (pin "1") (pinfunction "1_1") (pintype "passive"))
      (node (ref "C35") (pin "1") (pinfunction "1_1") (pintype "passive"))
      (node (ref "C36") (pin "1") (pinfunction "1_1") (pintype "passive"))
      (node (ref "C37") (pin "1") (pinfunction "1_1") (pintype "passive"))
      (node (ref "C38") (pin "2") (pinfunction "2_2") (pintype "passive"))
      (node (ref "C39") (pin "2") (pinfunction "2_2") (pintype "passive"))
      (node (ref "C63") (pin "2") (pinfunction "2_2") (pintype "passive"))
      (node (ref "C64") (pin "1") (pinfunction "1_1") (pintype "passive"))
      (node (ref "C78") (pin "1") (pinfunction "1_1") (pintype "passive"))
      (node (ref "J1") (pin "2") (pinfunction "SHIELD_2") (pintype "passive"))
      (node (ref "J2") (pin "2") (pinfunction "SHIELD_2") (pintype "passive"))
      (node (ref "J3") (pin "2") (pinfunction "SHIELD_2") (pintype "passive"))
      (node (ref "Q5") (pin "3") (pinfunction "S_3") (pintype "passive"))
      (node (ref "R122") (pin "1") (pinfunction "1_1") (pintype "passive"))
      (node (ref "R123") (pin "1") (pinfunction "1_1") (pintype "passive"))
      (node (ref "R124") (pin "3") (pinfunction "3_3") (pintype "passive"))
      (node (ref "R127") (pin "1") (pinfunction "1_1") (pintype "passive"))
      (node (ref "R18") (pin "1") (pinfunction "1_1") (pintype "passive"))
      (node (ref "R19") (pin "1") (pinfunction "1_1") (pintype "passive"))
      (node (ref "R24") (pin "1") (pinfunction "1_1") (pintype "passive"))
      (node (ref "R35") (pin "1") (pinfunction "1_1") (pintype "passive"))
      (node (ref "R41") (pin "1") (pinfunction "1_1") (pintype "passive"))
      (node (ref "SHLD3") (pin "1") (pinfunction "1_1") (pintype "passive"))
      (node (ref "U11") (pin "3") (pinfunction "C_3") (pintype "passive"))
      (node (ref "U11") (pin "4") (pinfunction "~{G2A}_4") (pintype "passive"))
      (node (ref "U11") (pin "5") (pinfunction "~{G2B}_5") (pintype "passive"))
      (node (ref "U11") (pin "8") (pinfunction "GND_8") (pintype "passive"))
      (node (ref "U7") (pin "17") (pinfunction "PAD_17") (pintype "power_in"))
      (node (ref "U7") (pin "5") (pinfunction "GND_5") (pintype "power_in"))
      (node (ref "U7") (pin "8") (pinfunction "GND_8") (pintype "power_in"))
      (node (ref "U9") (pin "14") (pinfunction "CLL_14") (pintype "passive"))
      (node (ref "U9") (pin "17") (pinfunction "PAD_17") (pintype "passive"))
    )
    (net (code "28") (name "Net-(C15-Pad1)") (class "Default")
      (node (ref "C15") (pin "1") (pinfunction "1_1") (pintype "passive"))
      (node (ref "C23") (pin "2") (pinfunction "2_2") (pintype "passive"))
      (node (ref "K1") (pin "7") (pinfunction "7_7") (pintype "passive"))
      (node (ref "R32") (pin "2") (pinfunction "2_2") (pintype "passive"))
      (node (ref "R35") (pin "2") (pinfunction "2_2") (pintype "passive"))
    )
    (net (code "29") (name "Net-(C15-Pad2)") (class "Default")
      (node (ref "C15") (pin "2") (pinfunction "2_2") (pintype "passive"))
      (node (ref "C16") (pin "2") (pinfunction "2_2") (pintype "passive"))
      (node (ref "C21") (pin "1") (pinfunction "1_1") (pintype "passive"))
    )
    (net (code "30") (name "Net-(C20-Pad1)") (class "Default")
      (node (ref "C20") (pin "1") (pinfunction "1_1") (pintype "passive"))
      (node (ref "R30") (pin "1") (pinfunction "1_1") (pintype "passive"))
      (node (ref "R31") (pin "2") (pinfunction "2_2") (pintype "passive"))
    )
    (net (code "31") (name "Net-(C21-Pad2)") (class "Default")
      (node (ref "C21") (pin "2") (pinfunction "2_2") (pintype "passive"))
      (node (ref "K1") (pin "2") (pinfunction "2_2") (pintype "passive"))
      (node (ref "R32") (pin "1") (pinfunction "1_1") (pintype "passive"))
    )
    (net (code "32") (name "Net-(C26-Pad2)") (class "Default")
      (node (ref "C26") (pin "2") (pinfunction "2_2") (pintype "passive"))
      (node (ref "R54") (pin "2") (pinfunction "2_2") (pintype "passive"))
    )
    (net (code "33") (name "Net-(J2-Signal)") (class "Default")
      (node (ref "J2") (pin "1") (pinfunction "Signal_1") (pintype "passive"))
      (node (ref "K2") (pin "3") (pinfunction "3_3") (pintype "passive"))
    )
    (net (code "34") (name "Net-(K1-Pad3)") (class "Default")
      (node (ref "K1") (pin "3") (pinfunction "3_3") (pintype "passive"))
      (node (ref "K2") (pin "6") (pinfunction "6_6") (pintype "passive"))
    )
    (net (code "35") (name "Net-(K1-Pad4)") (class "Default")
      (node (ref "K1") (pin "4") (pinfunction "4_4") (pintype "passive"))
      (node (ref "K1") (pin "5") (pinfunction "5_5") (pintype "passive"))
    )
    (net (code "36") (name "Net-(K2-Pad2)") (class "Default")
      (node (ref "K2") (pin "2") (pinfunction "2_2") (pintype "passive"))
      (node (ref "R31") (pin "1") (pinfunction "1_1") (pintype "passive"))
    )
    (net (code "37") (name "Net-(K2-Pad4)") (class "Default")
      (node (ref "K2") (pin "4") (pinfunction "4_4") (pintype "passive"))
      (node (ref "R29") (pin "1") (pinfunction "1_1") (pintype "passive"))
      (node (ref "R41") (pin "2") (pinfunction "2_2") (pintype "passive"))
    )
    (net (code "38") (name "Net-(K2-Pad5)") (class "Default")
      (node (ref "K2") (pin "5") (pinfunction "5_5") (pintype "passive"))
      (node (ref "R29") (pin "2") (pinfunction "2_2") (pintype "passive"))
    )
    (net (code "39") (name "Net-(K2-Pad7)") (class "Default")
      (node (ref "K2") (pin "7") (pinfunction "7_7") (pintype "passive"))
      (node (ref "R30") (pin "2") (pinfunction "2_2") (pintype "passive"))
    )
    (net (code "40") (name "Net-(Q5-G)") (class "Default")
      (node (ref "Q5") (pin "2") (pinfunction "G_2") (pintype "passive"))
      (node (ref "R126") (pin "1") (pinfunction "1_1") (pintype "passive"))
    )
    (net (code "41") (name "Net-(R121-Pad1)") (class "Default")
      (node (ref "R121") (pin "1") (pinfunction "1_1") (pintype "passive"))
      (node (ref "R123") (pin "2") (pinfunction "2_2") (pintype "passive"))
      (node (ref "R124") (pin "1") (pinfunction "1_1") (pintype "passive"))
      (node (ref "R124") (pin "2") (pinfunction "2_2") (pintype "passive"))
    )
    (net (code "42") (name "Net-(U7-IN_N)") (class "Default")
      (node (ref "C31") (pin "1") (pinfunction "1_1") (pintype "passive"))
      (node (ref "FB7") (pin "2") (pinfunction "2_2") (pintype "passive"))
      (node (ref "R118") (pin "1") (pinfunction "1_1") (pintype "passive"))
      (node (ref "R119") (pin "2") (pinfunction "2_2") (pintype "passive"))
      (node (ref "TP25") (pin "1") (pinfunction "1_1") (pintype "passive"))
      (node (ref "U7") (pin "7") (pinfunction "IN_N_7") (pintype "passive"))
    )
    (net (code "43") (name "Net-(U7-IN_P)") (class "Default")
      (node (ref "R56") (pin "2") (pinfunction "2_2") (pintype "passive"))
      (node (ref "U7") (pin "6") (pinfunction "IN_P_6") (pintype "passive"))
    )
    (net (code "44") (name "Net-(U9-IN)") (class "Default")
      (node (ref "C26") (pin "1") (pinfunction "1_1") (pintype "passive"))
      (node (ref "R65") (pin "2") (pinfunction "2_2") (pintype "passive"))
      (node (ref "U9") (pin "2") (pinfunction "IN_2") (pintype "passive"))
    )
    (net (code "45") (name "Net-(U9-IN_Aux)") (class "Default")
      (node (ref "C29") (pin "2") (pinfunction "2_2") (pintype "passive"))
      (node (ref "R100") (pin "1") (pinfunction "1_1") (pintype "passive"))
      (node (ref "U9") (pin "4") (pinfunction "IN_Aux_4") (pintype "passive"))
    )
    (net (code "46") (name "Net-(U9-IN_Bias)") (class "Default")
      (node (ref "R65") (pin "1") (pinfunction "1_1") (pintype "passive"))
      (node (ref "U9") (pin "3") (pinfunction "IN_Bias_3") (pintype "passive"))
    )
    (net (code "47") (name "Net-(U9-OUT)") (class "Default")
      (node (ref "R56") (pin "1") (pinfunction "1_1") (pintype "passive"))
      (node (ref "R98") (pin "2") (pinfunction "2_2") (pintype "passive"))
      (node (ref "U9") (pin "11") (pinfunction "OUT_11") (pintype "passive"))
    )
    (net (code "48") (name "Net-(U9-R_Bias)") (class "Default")
      (node (ref "R55") (pin "1") (pinfunction "1_1") (pintype "passive"))
      (node (ref "U9") (pin "7") (pinfunction "R_Bias_7") (pintype "passive"))
    )
    (net (code "49") (name "Net-(U10-COM)") (class "Default")
      (node (ref "C27") (pin "2") (pinfunction "2_2") (pintype "passive"))
      (node (ref "R122") (pin "2") (pinfunction "2_2") (pintype "passive"))
      (node (ref "U10") (pin "1") (pinfunction "COM_1") (pintype "passive"))
      (node (ref "U18") (pin "3") (pinfunction "+_3") (pintype "passive"))
    )
    (net (code "50") (name "Net-(U10-NO)") (class "Default")
      (node (ref "C27") (pin "1") (pinfunction "1_1") (pintype "passive"))
      (node (ref "R96") (pin "1") (pinfunction "1_1") (pintype "passive"))
      (node (ref "U10") (pin "2") (pinfunction "NO_2") (pintype "passive"))
    )
    (net (code "51") (name "Net-(U11-Y0)") (class "Default")
      (node (ref "R17") (pin "1") (pinfunction "1_1") (pintype "passive"))
      (node (ref "U11") (pin "15") (pinfunction "Y0_15") (pintype "passive"))
    )
    (net (code "52") (name "Net-(U11-Y1)") (class "Default")
      (node (ref "R16") (pin "1") (pinfunction "1_1") (pintype "passive"))
      (node (ref "U11") (pin "14") (pinfunction "Y1_14") (pintype "passive"))
    )
    (net (code "53") (name "Net-(U11-Y2)") (class "Default")
      (node (ref "R15") (pin "1") (pinfunction "1_1") (pintype "passive"))
      (node (ref "U11") (pin "13") (pinfunction "Y2_13") (pintype "passive"))
    )
    (net (code "54") (name "Net-(U11-Y3)") (class "Default")
      (node (ref "R5") (pin "1") (pinfunction "1_1") (pintype "passive"))
      (node (ref "U11") (pin "12") (pinfunction "Y3_12") (pintype "passive"))
    )
    (net (code "55") (name "Net-(U18--)") (class "Default")
      (node (ref "C30") (pin "2") (pinfunction "2_2") (pintype "passive"))
      (node (ref "R121") (pin "2") (pinfunction "2_2") (pintype "passive"))
      (node (ref "R98") (pin "1") (pinfunction "1_1") (pintype "passive"))
      (node (ref "R99") (pin "2") (pinfunction "2_2") (pintype "passive"))
      (node (ref "U18") (pin "2") (pinfunction "-_2") (pintype "passive"))
    )
    (net (code "56") (name "Net-(U18-OUT)") (class "Default")
      (node (ref "C30") (pin "1") (pinfunction "1_1") (pintype "passive"))
      (node (ref "R100") (pin "2") (pinfunction "2_2") (pintype "passive"))
      (node (ref "U18") (pin "6") (pinfunction "OUT_6") (pintype "passive"))
    )
    (net (code "57") (name "unconnected-(U7-AUX_N-Pad2)") (class "Default")
      (node (ref "U7") (pin "2") (pinfunction "AUX_N_2") (pintype "passive+no_connect"))
    )
    (net (code "58") (name "unconnected-(U7-AUX_P-Pad1)") (class "Default")
      (node (ref "U7") (pin "1") (pinfunction "AUX_P_1") (pintype "passive+no_connect"))
    )
    (net (code "59") (name "unconnected-(U7-AUX_VCM-Pad16)") (class "Default")
      (node (ref "U7") (pin "16") (pinfunction "AUX_VCM_16") (pintype "input+no_connect"))
    )
    (net (code "60") (name "unconnected-(U9-NC-Pad9)") (class "Default")
      (node (ref "U9") (pin "9") (pinfunction "NC_9") (pintype "passive+no_connect"))
    )
    (net (code "61") (name "unconnected-(U9-NC-Pad13)") (class "Default")
      (node (ref "U9") (pin "13") (pinfunction "NC_13") (pintype "passive+no_connect"))
    )
    (net (code "62") (name "unconnected-(U9-NC-Pad16)") (class "Default")
      (node (ref "U9") (pin "16") (pinfunction "NC_16") (pintype "passive+no_connect"))
    )
    (net (code "63") (name "unconnected-(U11-Y4-Pad11)") (class "Default")
      (node (ref "U11") (pin "11") (pinfunction "Y4_11") (pintype "passive+no_connect"))
    )
    (net (code "64") (name "unconnected-(U11-Y5-Pad10)") (class "Default")
      (node (ref "U11") (pin "10") (pinfunction "Y5_10") (pintype "passive+no_connect"))
    )
    (net (code "65") (name "unconnected-(U11-Y6-Pad9)") (class "Default")
      (node (ref "U11") (pin "9") (pinfunction "Y6_9") (pintype "passive+no_connect"))
    )
    (net (code "66") (name "unconnected-(U11-Y7-Pad7)") (class "Default")
      (node (ref "U11") (pin "7") (pinfunction "Y7_7") (pintype "passive+no_connect"))
    )
    (net (code "67") (name "unconnected-(U18-N1-Pad1)") (class "Default")
      (node (ref "U18") (pin "1") (pinfunction "N1_1") (pintype "passive+no_connect"))
    )
    (net (code "68") (name "unconnected-(U18-N2-Pad8)") (class "Default")
      (node (ref "U18") (pin "8") (pinfunction "N2_8") (pintype "passive+no_connect"))
    )
  )
)
